# LTC3105Board.net
KiCad netlist of a schematic drawn in EAGLE
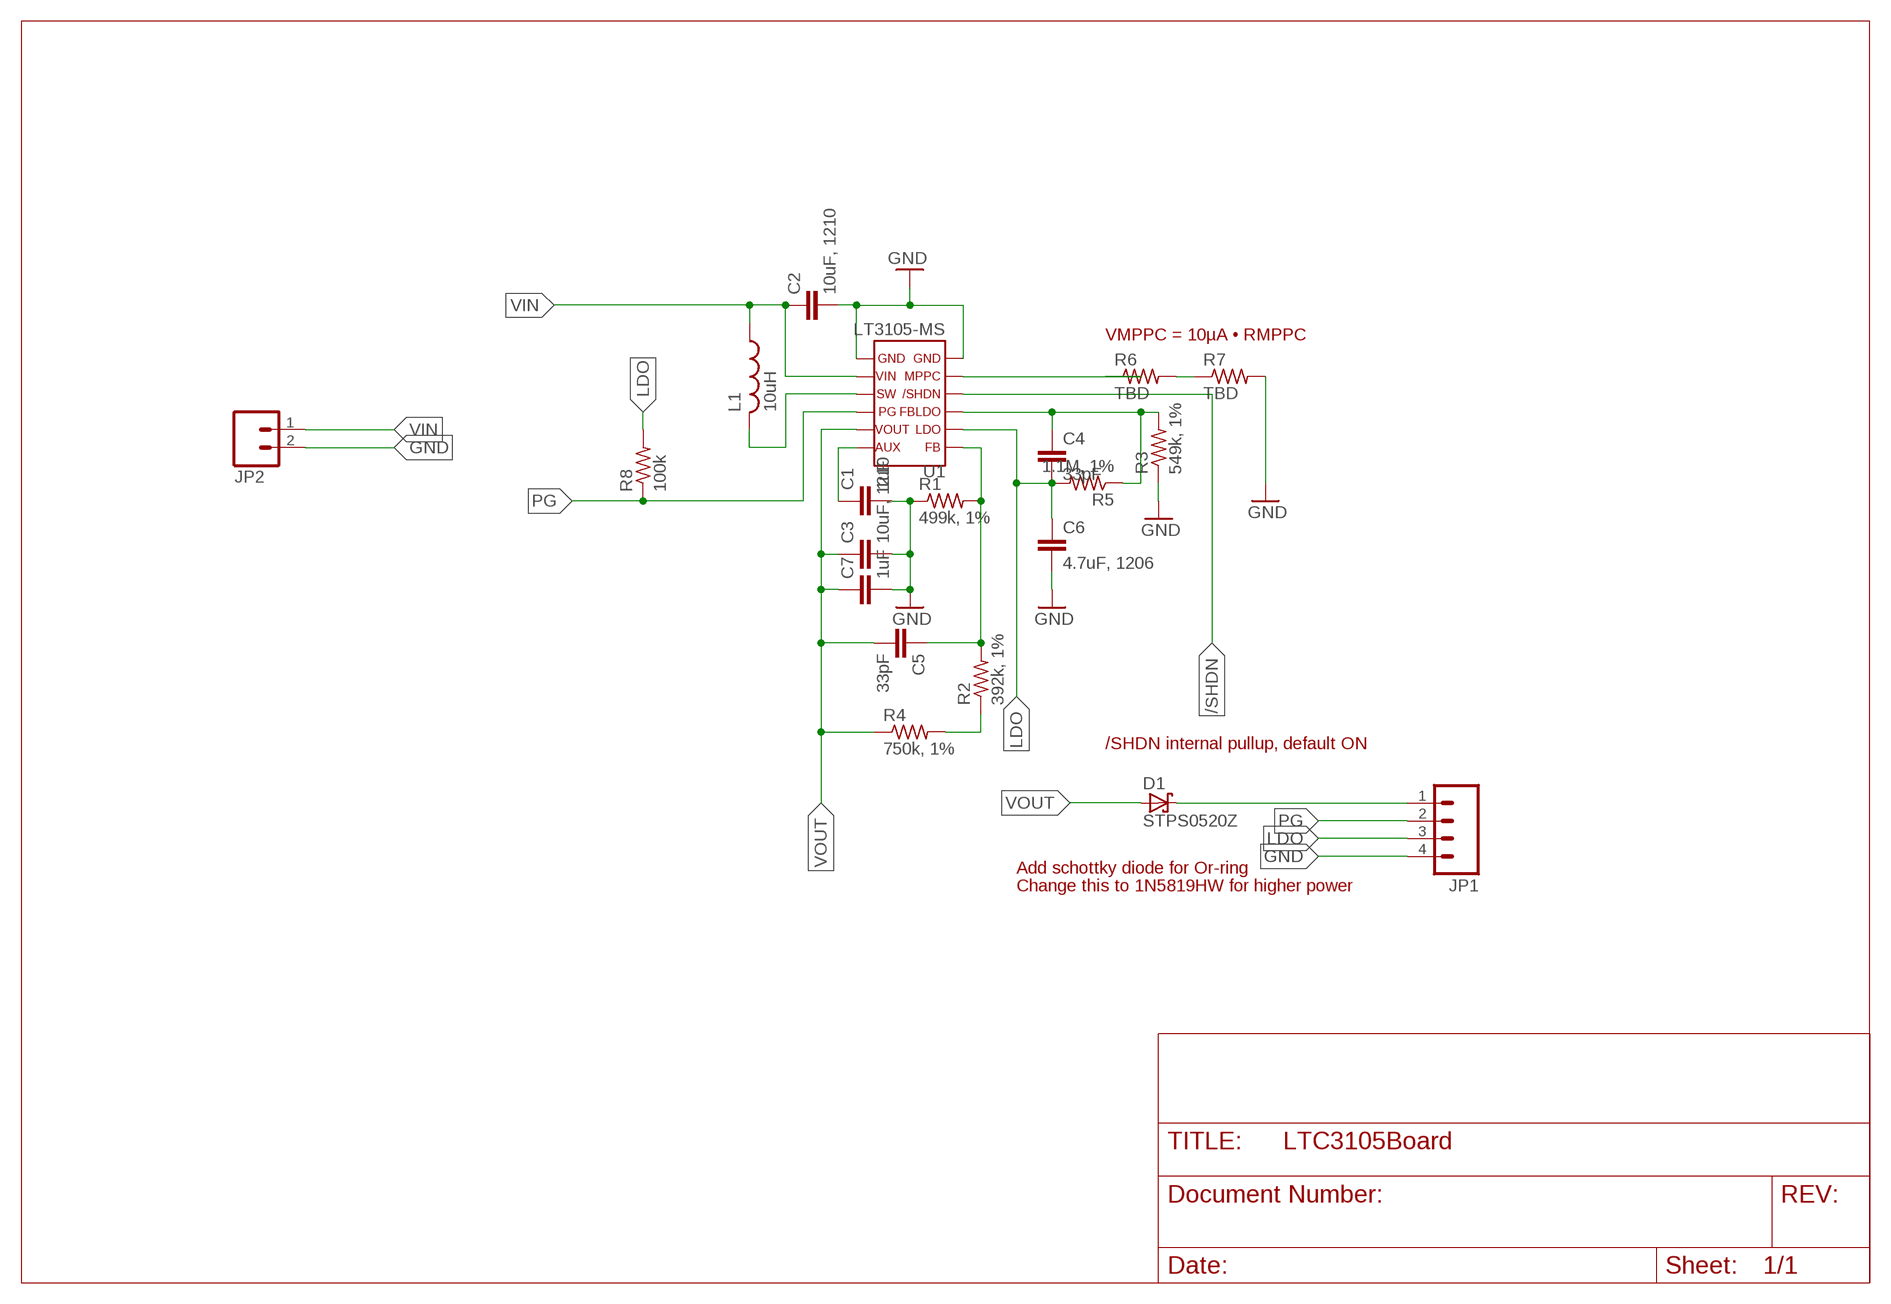
[diagram p0: schematic, sheet 1]

(export (version "E")
  (design (tool "Eeschema 10.0.6"))
  (components
    (comp (ref "C1")
      (value "1uF")
      (footprint "eagle-import:C0603(1608)")
      (libsource (lib "eagle-import") (part "C0603(1608)"))
    )
    (comp (ref "C2")
      (value "10uF, 1210")
      (footprint "eagle-import:C1210-GCM32")
      (libsource (lib "eagle-import") (part "C1210(3225)-GCM32"))
    )
    (comp (ref "C3")
      (value "10uF, 1210")
      (footprint "eagle-import:C1210-GCM32")
      (libsource (lib "eagle-import") (part "C1210(3225)-GCM32"))
    )
    (comp (ref "C4")
      (value "33pF")
      (footprint "eagle-import:C0603(1608)")
      (libsource (lib "eagle-import") (part "C0603(1608)"))
    )
    (comp (ref "C5")
      (value "33pF")
      (footprint "eagle-import:C0603(1608)")
      (libsource (lib "eagle-import") (part "C0603(1608)"))
    )
    (comp (ref "C6")
      (value "4.7uF, 1206")
      (footprint "eagle-import:C1206-GCM31")
      (libsource (lib "eagle-import") (part "C1206(3216)-GCM31"))
    )
    (comp (ref "C7")
      (value "1uF")
      (footprint "eagle-import:C0603(1608)")
      (libsource (lib "eagle-import") (part "C0603(1608)"))
    )
    (comp (ref "D1")
      (value "STPS0520Z")
      (footprint "eagle-import:SOD-123")
      (libsource (lib "eagle-import") (part "STPS0520Z"))
    )
    (comp (ref "JP1")
      (value "M04PTH")
      (footprint "eagle-import:1X04")
      (libsource (lib "eagle-import") (part "M04PTH"))
    )
    (comp (ref "JP2")
      (value "M02PTH")
      (footprint "eagle-import:1X02")
      (libsource (lib "eagle-import") (part "M02PTH"))
    )
    (comp (ref "L1")
      (value "10uH")
      (footprint "eagle-import:CDRH3D18")
      (libsource (lib "eagle-import") (part "L"))
    )
    (comp (ref "R1")
      (value "499k, 1%")
      (footprint "eagle-import:R0603(1608)")
      (libsource (lib "eagle-import") (part "R0603(1608)"))
    )
    (comp (ref "R2")
      (value "392k, 1%")
      (footprint "eagle-import:R0603(1608)")
      (libsource (lib "eagle-import") (part "R0603(1608)"))
    )
    (comp (ref "R3")
      (value "549k, 1%")
      (footprint "eagle-import:R0603(1608)")
      (libsource (lib "eagle-import") (part "R0603(1608)"))
    )
    (comp (ref "R4")
      (value "750k, 1%")
      (footprint "eagle-import:R0603(1608)")
      (libsource (lib "eagle-import") (part "R0603(1608)"))
    )
    (comp (ref "R5")
      (value "1.1M, 1%")
      (footprint "eagle-import:R0603(1608)")
      (libsource (lib "eagle-import") (part "R0603(1608)"))
    )
    (comp (ref "R6")
      (value "TBD")
      (footprint "eagle-import:R0603(1608)")
      (libsource (lib "eagle-import") (part "R0603(1608)"))
    )
    (comp (ref "R7")
      (value "TBD")
      (footprint "eagle-import:R0603(1608)")
      (libsource (lib "eagle-import") (part "R0603(1608)"))
    )
    (comp (ref "R8")
      (value "100k")
      (footprint "eagle-import:R0603(1608)")
      (libsource (lib "eagle-import") (part "R0603(1608)"))
    )
    (comp (ref "U1")
      (value "LT3105-MS")
      (footprint "eagle-import:MSOP-12-MS")
      (libsource (lib "eagle-import") (part "LT3105-MS"))
    )
  )
  (nets
    (net (code "1") (name "GND") (class "Default")
      (node (ref "C1") (pin "2") (pinfunction "2_2") (pintype "passive"))
      (node (ref "C2") (pin "P$2") (pinfunction "2_P$2") (pintype "passive"))
      (node (ref "C3") (pin "P$2") (pinfunction "2_P$2") (pintype "passive"))
      (node (ref "C6") (pin "P$2") (pinfunction "2_P$2") (pintype "passive"))
      (node (ref "C7") (pin "2") (pinfunction "2_2") (pintype "passive"))
      (node (ref "JP1") (pin "4") (pinfunction "4_4") (pintype "passive"))
      (node (ref "JP2") (pin "2") (pinfunction "2_2") (pintype "passive"))
      (node (ref "R1") (pin "1") (pinfunction "1_1") (pintype "passive"))
      (node (ref "R3") (pin "1") (pinfunction "1_1") (pintype "passive"))
      (node (ref "R7") (pin "2") (pinfunction "2_2") (pintype "passive"))
      (node (ref "U1") (pin "6") (pinfunction "P$6_6") (pintype "bidirectional"))
      (node (ref "U1") (pin "7") (pinfunction "P$7_7") (pintype "bidirectional"))
    )
    (net (code "2") (name "LDO") (class "Default")
      (node (ref "C4") (pin "2") (pinfunction "2_2") (pintype "passive"))
      (node (ref "C6") (pin "P$1") (pinfunction "1_P$1") (pintype "passive"))
      (node (ref "JP1") (pin "3") (pinfunction "3_3") (pintype "passive"))
      (node (ref "R5") (pin "2") (pinfunction "2_2") (pintype "passive"))
      (node (ref "R8") (pin "2") (pinfunction "2_2") (pintype "passive"))
      (node (ref "U1") (pin "2") (pinfunction "P$2_2") (pintype "bidirectional"))
    )
    (net (code "3") (name "Net-(D1-PadC)") (class "Default")
      (node (ref "D1") (pin "C") (pinfunction "C_C") (pintype "passive"))
      (node (ref "JP1") (pin "1") (pinfunction "1_1") (pintype "passive"))
    )
    (net (code "4") (name "Net-(L1-2)") (class "Default")
      (node (ref "L1") (pin "P$2") (pinfunction "2_P$2") (pintype "passive"))
      (node (ref "U1") (pin "9") (pinfunction "P$9_9") (pintype "bidirectional"))
    )
    (net (code "5") (name "Net-(R2-Pad1)") (class "Default")
      (node (ref "R2") (pin "1") (pinfunction "1_1") (pintype "passive"))
      (node (ref "R4") (pin "2") (pinfunction "2_2") (pintype "passive"))
    )
    (net (code "6") (name "Net-(R6-Pad2)") (class "Default")
      (node (ref "R6") (pin "2") (pinfunction "2_2") (pintype "passive"))
      (node (ref "R7") (pin "1") (pinfunction "1_1") (pintype "passive"))
    )
    (net (code "7") (name "Net-(U1-P$1)") (class "Default")
      (node (ref "C5") (pin "1") (pinfunction "1_1") (pintype "passive"))
      (node (ref "R1") (pin "2") (pinfunction "2_2") (pintype "passive"))
      (node (ref "R2") (pin "2") (pinfunction "2_2") (pintype "passive"))
      (node (ref "U1") (pin "1") (pinfunction "P$1_1") (pintype "bidirectional"))
    )
    (net (code "8") (name "Net-(U1-P$3)") (class "Default")
      (node (ref "C4") (pin "1") (pinfunction "1_1") (pintype "passive"))
      (node (ref "R3") (pin "2") (pinfunction "2_2") (pintype "passive"))
      (node (ref "R5") (pin "1") (pinfunction "1_1") (pintype "passive"))
      (node (ref "U1") (pin "3") (pinfunction "P$3_3") (pintype "bidirectional"))
    )
    (net (code "9") (name "Net-(U1-P$5)") (class "Default")
      (node (ref "R6") (pin "1") (pinfunction "1_1") (pintype "passive"))
      (node (ref "U1") (pin "5") (pinfunction "P$5_5") (pintype "bidirectional"))
    )
    (net (code "10") (name "Net-(U1-P$12)") (class "Default")
      (node (ref "C1") (pin "1") (pinfunction "1_1") (pintype "passive"))
      (node (ref "U1") (pin "12") (pinfunction "P$12_12") (pintype "bidirectional"))
    )
    (net (code "11") (name "PG") (class "Default")
      (node (ref "JP1") (pin "2") (pinfunction "2_2") (pintype "passive"))
      (node (ref "R8") (pin "1") (pinfunction "1_1") (pintype "passive"))
      (node (ref "U1") (pin "10") (pinfunction "P$10_10") (pintype "bidirectional"))
    )
    (net (code "12") (name "VIN") (class "Default")
      (node (ref "C2") (pin "P$1") (pinfunction "1_P$1") (pintype "passive"))
      (node (ref "JP2") (pin "1") (pinfunction "1_1") (pintype "passive"))
      (node (ref "L1") (pin "P$1") (pinfunction "1_P$1") (pintype "passive"))
      (node (ref "U1") (pin "8") (pinfunction "P$8_8") (pintype "bidirectional"))
    )
    (net (code "13") (name "VOUT") (class "Default")
      (node (ref "C3") (pin "P$1") (pinfunction "1_P$1") (pintype "passive"))
      (node (ref "C5") (pin "2") (pinfunction "2_2") (pintype "passive"))
      (node (ref "C7") (pin "1") (pinfunction "1_1") (pintype "passive"))
      (node (ref "D1") (pin "A") (pinfunction "A_A") (pintype "passive"))
      (node (ref "R4") (pin "1") (pinfunction "1_1") (pintype "passive"))
      (node (ref "U1") (pin "11") (pinfunction "P$11_11") (pintype "bidirectional"))
    )
    (net (code "14") (name "{slash}SHDN") (class "Default")
      (node (ref "U1") (pin "4") (pinfunction "P$4_4") (pintype "bidirectional"))
    )
  )
)
